# Standalone_Control_Board.net
KiCad netlist of a schematic drawn in EAGLE
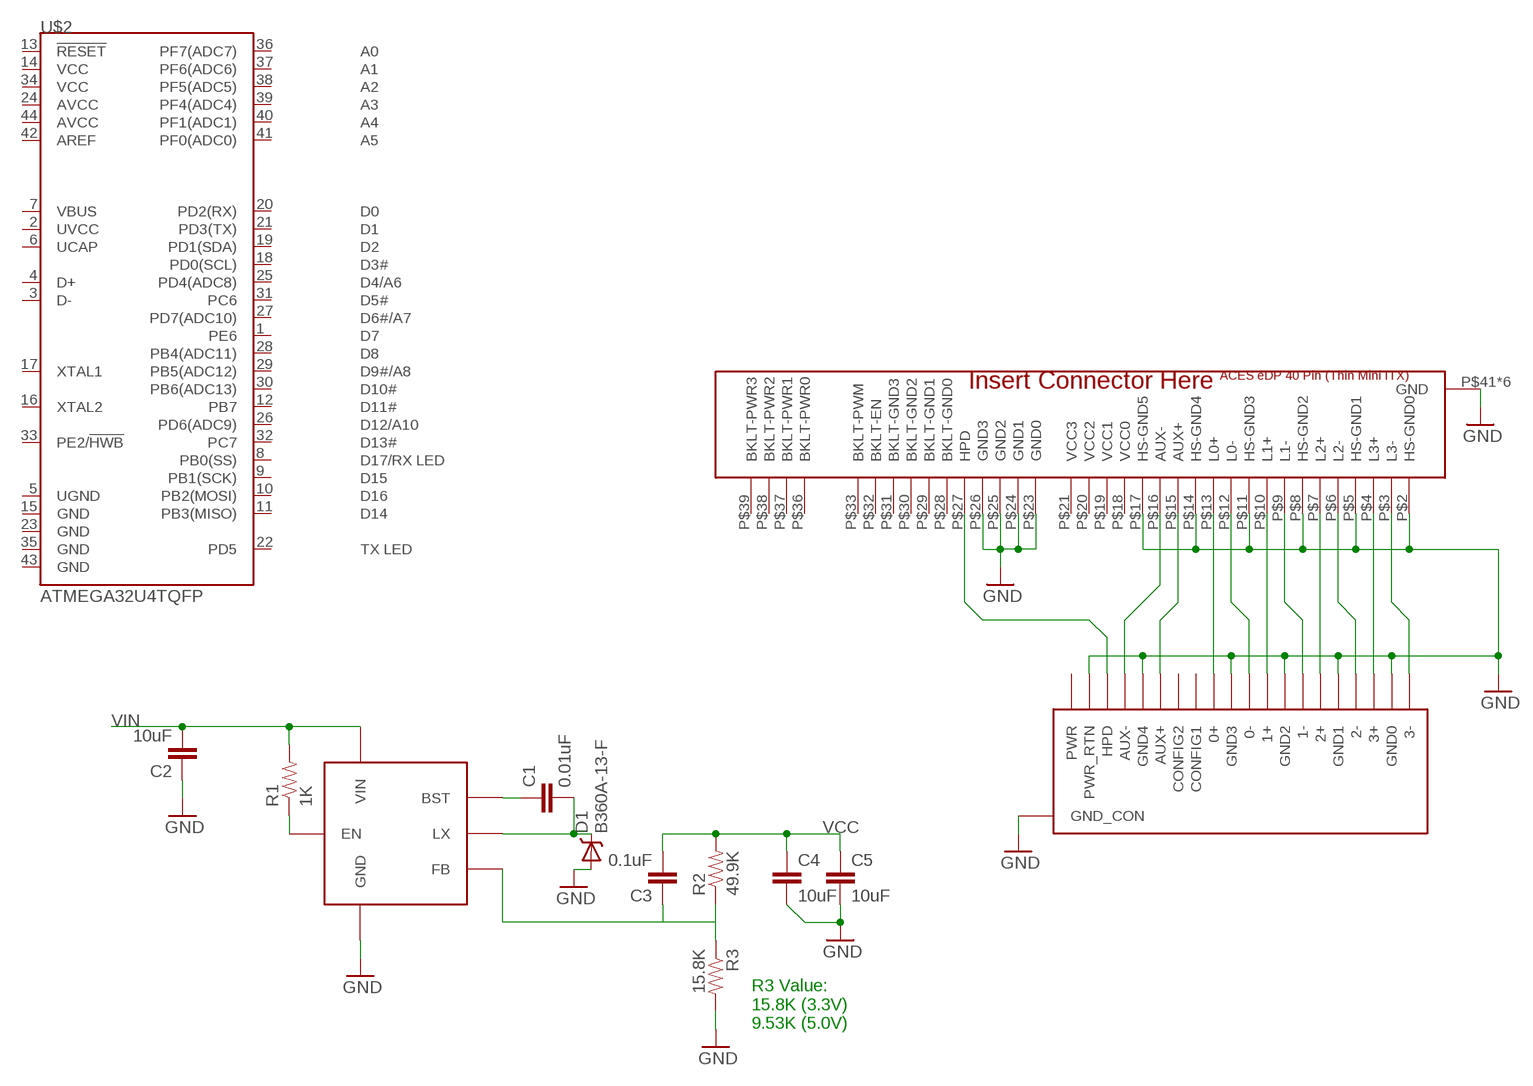
[diagram p0: schematic, sheet 1]

(export (version "E")
  (design (tool "Eeschema 10.0.6"))
  (components
    (comp (ref "C1")
      (value "0.01uF")
      (footprint "eagle-import:0805")
      (libsource (lib "eagle-import") (part "CAP0805"))
    )
    (comp (ref "C2")
      (value "10uF")
      (footprint "eagle-import:0805")
      (libsource (lib "eagle-import") (part "CAP0805"))
    )
    (comp (ref "C3")
      (value "0.1uF")
      (footprint "eagle-import:0805")
      (libsource (lib "eagle-import") (part "CAP0805"))
    )
    (comp (ref "C4")
      (value "10uF")
      (footprint "eagle-import:0805")
      (libsource (lib "eagle-import") (part "CAP0805"))
    )
    (comp (ref "C5")
      (value "10uF")
      (footprint "eagle-import:0805")
      (libsource (lib "eagle-import") (part "CAP0805"))
    )
    (comp (ref "D1")
      (value "B360A-13-F")
      (footprint "eagle-import:SMA-DIODE")
      (libsource (lib "eagle-import") (part "DIODE-SCHOTTKY_"))
    )
    (comp (ref "F1")
      (value "EDP-40PIN-ACES")
      (footprint "eagle-import:ACES-50203-040")
      (libsource (lib "eagle-import") (part "EDP-40PIN-ACES"))
    )
    (comp (ref "R1")
      (value "1K")
      (footprint "eagle-import:0805")
      (libsource (lib "eagle-import") (part "RESISTOR0805-RES"))
    )
    (comp (ref "R2")
      (value "49.9K")
      (footprint "eagle-import:0805")
      (libsource (lib "eagle-import") (part "RESISTOR0805-RES"))
    )
    (comp (ref "R3")
      (value "15.8K")
      (footprint "eagle-import:0805")
      (libsource (lib "eagle-import") (part "RESISTOR0805-RES"))
    )
    (comp (ref "U$1")
      (value "DP-SINK")
      (footprint "eagle-import:MOLEX-47272-0001")
      (libsource (lib "eagle-import") (part "DP-SINK"))
    )
    (comp (ref "U$2")
      (value "ATMEGA32U4TQFP")
      (footprint "eagle-import:SPARKFUN-DIGITALIC_TQFP44")
      (libsource (lib "eagle-import") (part "ATMEGA32U4TQFP"))
    )
    (comp (ref "U$3")
      (value "AOZ1281-BUCK")
      (footprint "eagle-import:2X2-DFN")
      (libsource (lib "eagle-import") (part "AOZ1281-BUCK"))
    )
  )
  (nets
    (net (code "1") (name "/BKLT-GND0") (class "Default")
      (node (ref "F1") (pin "P$28") (pinfunction "BKLT-GND0_P$28") (pintype "power_in"))
    )
    (net (code "2") (name "/BKLT-GND1") (class "Default")
      (node (ref "F1") (pin "P$29") (pinfunction "BKLT-GND1_P$29") (pintype "power_in"))
    )
    (net (code "3") (name "/BKLT-GND2") (class "Default")
      (node (ref "F1") (pin "P$30") (pinfunction "BKLT-GND2_P$30") (pintype "power_in"))
    )
    (net (code "4") (name "/BKLT-GND3") (class "Default")
      (node (ref "F1") (pin "P$31") (pinfunction "BKLT-GND3_P$31") (pintype "power_in"))
    )
    (net (code "5") (name "/BKLT-PWR0") (class "Default")
      (node (ref "F1") (pin "P$36") (pinfunction "BKLT-PWR0_P$36") (pintype "power_in"))
    )
    (net (code "6") (name "/BKLT-PWR1") (class "Default")
      (node (ref "F1") (pin "P$37") (pinfunction "BKLT-PWR1_P$37") (pintype "power_in"))
    )
    (net (code "7") (name "/BKLT-PWR2") (class "Default")
      (node (ref "F1") (pin "P$38") (pinfunction "BKLT-PWR2_P$38") (pintype "power_in"))
    )
    (net (code "8") (name "/BKLT-PWR3") (class "Default")
      (node (ref "F1") (pin "P$39") (pinfunction "BKLT-PWR3_P$39") (pintype "power_in"))
    )
    (net (code "9") (name "/PWR") (class "Default")
      (node (ref "U$1") (pin "P$24") (pinfunction "PWR_P$24") (pintype "power_in"))
    )
    (net (code "10") (name "/VCC") (class "Default")
      (node (ref "C3") (pin "2") (pinfunction "2_2") (pintype "passive"))
      (node (ref "C4") (pin "1") (pinfunction "1_1") (pintype "passive"))
      (node (ref "C5") (pin "1") (pinfunction "1_1") (pintype "passive"))
      (node (ref "R2") (pin "2") (pinfunction "2_2") (pintype "passive"))
    )
    (net (code "11") (name "/VCC0") (class "Default")
      (node (ref "F1") (pin "P$18") (pinfunction "VCC0_P$18") (pintype "power_in"))
    )
    (net (code "12") (name "/VCC1") (class "Default")
      (node (ref "F1") (pin "P$19") (pinfunction "VCC1_P$19") (pintype "power_in"))
    )
    (net (code "13") (name "/VCC2") (class "Default")
      (node (ref "F1") (pin "P$20") (pinfunction "VCC2_P$20") (pintype "power_in"))
    )
    (net (code "14") (name "/VCC3") (class "Default")
      (node (ref "F1") (pin "P$21") (pinfunction "VCC3_P$21") (pintype "power_in"))
    )
    (net (code "15") (name "/VIN") (class "Default")
      (node (ref "C2") (pin "2") (pinfunction "2_2") (pintype "passive"))
      (node (ref "R1") (pin "2") (pinfunction "2_2") (pintype "passive"))
      (node (ref "U$3") (pin "2") (pinfunction "VIN_2") (pintype "bidirectional"))
      (node (ref "U$3") (pin "3") (pinfunction "VIN_3") (pintype "bidirectional"))
    )
    (net (code "16") (name "GND") (class "Default")
      (node (ref "C2") (pin "1") (pinfunction "1_1") (pintype "passive"))
      (node (ref "C4") (pin "2") (pinfunction "2_2") (pintype "passive"))
      (node (ref "C5") (pin "2") (pinfunction "2_2") (pintype "passive"))
      (node (ref "D1") (pin "A") (pinfunction "A_A") (pintype "passive"))
      (node (ref "F1") (pin "P$11") (pinfunction "HS-GND3_P$11") (pintype "tri_state"))
      (node (ref "F1") (pin "P$14") (pinfunction "HS-GND4_P$14") (pintype "tri_state"))
      (node (ref "F1") (pin "P$17") (pinfunction "HS-GND5_P$17") (pintype "tri_state"))
      (node (ref "F1") (pin "P$2") (pinfunction "HS-GND0_P$2") (pintype "tri_state"))
      (node (ref "F1") (pin "P$23") (pinfunction "GND0_P$23") (pintype "power_in"))
      (node (ref "F1") (pin "P$24") (pinfunction "GND1_P$24") (pintype "power_in"))
      (node (ref "F1") (pin "P$25") (pinfunction "GND2_P$25") (pintype "power_in"))
      (node (ref "F1") (pin "P$26") (pinfunction "GND3_P$26") (pintype "power_in"))
      (node (ref "F1") (pin "P$41") (pinfunction "GND_P$41") (pintype "power_in"))
      (node (ref "F1") (pin "P$42") (pinfunction "GND_P$42") (pintype "power_in"))
      (node (ref "F1") (pin "P$43") (pinfunction "GND_P$43") (pintype "power_in"))
      (node (ref "F1") (pin "P$44") (pinfunction "GND_P$44") (pintype "power_in"))
      (node (ref "F1") (pin "P$45") (pinfunction "GND_P$45") (pintype "power_in"))
      (node (ref "F1") (pin "P$46") (pinfunction "GND_P$46") (pintype "power_in"))
      (node (ref "F1") (pin "P$5") (pinfunction "HS-GND1_P$5") (pintype "tri_state"))
      (node (ref "F1") (pin "P$8") (pinfunction "HS-GND2_P$8") (pintype "tri_state"))
      (node (ref "R3") (pin "2") (pinfunction "2_2") (pintype "passive"))
      (node (ref "U$1") (pin "GND1") (pinfunction "GND_CON_GND1") (pintype "power_in"))
      (node (ref "U$1") (pin "GND2") (pinfunction "GND_CON_GND2") (pintype "power_in"))
      (node (ref "U$1") (pin "GND3") (pinfunction "GND_CON_GND3") (pintype "power_in"))
      (node (ref "U$1") (pin "GND4") (pinfunction "GND_CON_GND4") (pintype "power_in"))
      (node (ref "U$1") (pin "P$12") (pinfunction "GND2_P$12") (pintype "power_in"))
      (node (ref "U$1") (pin "P$15") (pinfunction "GND3_P$15") (pintype "power_in"))
      (node (ref "U$1") (pin "P$20") (pinfunction "GND4_P$20") (pintype "power_in"))
      (node (ref "U$1") (pin "P$23") (pinfunction "PWR_RTN_P$23") (pintype "power_in"))
      (node (ref "U$1") (pin "P$6") (pinfunction "GND0_P$6") (pintype "power_in"))
      (node (ref "U$1") (pin "P$9") (pinfunction "GND1_P$9") (pintype "power_in"))
      (node (ref "U$3") (pin "6") (pinfunction "GND_6") (pintype "bidirectional"))
      (node (ref "U$3") (pin "7") (pinfunction "GND_7") (pintype "bidirectional"))
      (node (ref "U$3") (pin "CENTER") (pinfunction "GND_CENTER") (pintype "bidirectional"))
    )
    (net (code "17") (name "Net-(F1-AUX+)") (class "Default")
      (node (ref "F1") (pin "P$15") (pinfunction "AUX+_P$15") (pintype "tri_state"))
      (node (ref "U$1") (pin "P$19") (pinfunction "AUX+_P$19") (pintype "bidirectional"))
    )
    (net (code "18") (name "Net-(F1-AUX-)") (class "Default")
      (node (ref "F1") (pin "P$16") (pinfunction "AUX-_P$16") (pintype "tri_state"))
      (node (ref "U$1") (pin "P$21") (pinfunction "AUX-_P$21") (pintype "bidirectional"))
    )
    (net (code "19") (name "Net-(F1-HPD)") (class "Default")
      (node (ref "F1") (pin "P$27") (pinfunction "HPD_P$27") (pintype "bidirectional"))
      (node (ref "U$1") (pin "P$22") (pinfunction "HPD_P$22") (pintype "output"))
    )
    (net (code "20") (name "Net-(F1-L0+)") (class "Default")
      (node (ref "F1") (pin "P$13") (pinfunction "L0+_P$13") (pintype "tri_state"))
      (node (ref "U$1") (pin "P$16") (pinfunction "0+_P$16") (pintype "input"))
    )
    (net (code "21") (name "Net-(F1-L0-)") (class "Default")
      (node (ref "F1") (pin "P$12") (pinfunction "L0-_P$12") (pintype "tri_state"))
      (node (ref "U$1") (pin "P$14") (pinfunction "0-_P$14") (pintype "input"))
    )
    (net (code "22") (name "Net-(F1-L1+)") (class "Default")
      (node (ref "F1") (pin "P$10") (pinfunction "L1+_P$10") (pintype "tri_state"))
      (node (ref "U$1") (pin "P$13") (pinfunction "1+_P$13") (pintype "input"))
    )
    (net (code "23") (name "Net-(F1-L1-)") (class "Default")
      (node (ref "F1") (pin "P$9") (pinfunction "L1-_P$9") (pintype "tri_state"))
      (node (ref "U$1") (pin "P$11") (pinfunction "1-_P$11") (pintype "input"))
    )
    (net (code "24") (name "Net-(F1-L2+)") (class "Default")
      (node (ref "F1") (pin "P$7") (pinfunction "L2+_P$7") (pintype "tri_state"))
      (node (ref "U$1") (pin "P$10") (pinfunction "2+_P$10") (pintype "input"))
    )
    (net (code "25") (name "Net-(F1-L2-)") (class "Default")
      (node (ref "F1") (pin "P$6") (pinfunction "L2-_P$6") (pintype "tri_state"))
      (node (ref "U$1") (pin "P$8") (pinfunction "2-_P$8") (pintype "input"))
    )
    (net (code "26") (name "Net-(F1-L3+)") (class "Default")
      (node (ref "F1") (pin "P$4") (pinfunction "L3+_P$4") (pintype "tri_state"))
      (node (ref "U$1") (pin "P$7") (pinfunction "3+_P$7") (pintype "input"))
    )
    (net (code "27") (name "Net-(F1-L3-)") (class "Default")
      (node (ref "F1") (pin "P$3") (pinfunction "L3-_P$3") (pintype "tri_state"))
      (node (ref "U$1") (pin "P$5") (pinfunction "3-_P$5") (pintype "input"))
    )
    (net (code "28") (name "Net-(R2-Pad1)") (class "Default")
      (node (ref "R2") (pin "1") (pinfunction "1_1") (pintype "passive"))
      (node (ref "R3") (pin "1") (pinfunction "1_1") (pintype "passive"))
    )
    (net (code "29") (name "Net-(U$3-BST)") (class "Default")
      (node (ref "C1") (pin "1") (pinfunction "1_1") (pintype "passive"))
      (node (ref "U$3") (pin "8") (pinfunction "BST_8") (pintype "bidirectional"))
    )
    (net (code "30") (name "Net-(U$3-EN)") (class "Default")
      (node (ref "R1") (pin "1") (pinfunction "1_1") (pintype "passive"))
      (node (ref "U$3") (pin "4") (pinfunction "EN_4") (pintype "bidirectional"))
    )
    (net (code "31") (name "Net-(U$3-FB)") (class "Default")
      (node (ref "C3") (pin "1") (pinfunction "1_1") (pintype "passive"))
      (node (ref "U$3") (pin "5") (pinfunction "FB_5") (pintype "bidirectional"))
    )
    (net (code "32") (name "Net-(U$3-LX)") (class "Default")
      (node (ref "C1") (pin "2") (pinfunction "2_2") (pintype "passive"))
      (node (ref "D1") (pin "C") (pinfunction "C_C") (pintype "passive"))
      (node (ref "U$3") (pin "1") (pinfunction "LX_1") (pintype "bidirectional"))
    )
    (net (code "33") (name "unconnected-(F1-BKLT-EN-PadP$32)") (class "Default")
      (node (ref "F1") (pin "P$32") (pinfunction "BKLT-EN_P$32") (pintype "bidirectional"))
    )
    (net (code "34") (name "unconnected-(F1-BKLT-PWM-PadP$33)") (class "Default")
      (node (ref "F1") (pin "P$33") (pinfunction "BKLT-PWM_P$33") (pintype "bidirectional"))
    )
    (net (code "35") (name "unconnected-(U$1-CONFIG1-PadP$17)") (class "Default")
      (node (ref "U$1") (pin "P$17") (pinfunction "CONFIG1_P$17") (pintype "bidirectional"))
    )
    (net (code "36") (name "unconnected-(U$1-CONFIG2-PadP$18)") (class "Default")
      (node (ref "U$1") (pin "P$18") (pinfunction "CONFIG2_P$18") (pintype "bidirectional"))
    )
    (net (code "37") (name "unconnected-(U$2-AREF-Pad42)") (class "Default")
      (node (ref "U$2") (pin "42") (pinfunction "AREF_42") (pintype "bidirectional"))
    )
    (net (code "38") (name "unconnected-(U$2-AVCC-Pad24)") (class "Default")
      (node (ref "U$2") (pin "24") (pinfunction "AVCC_24") (pintype "bidirectional"))
    )
    (net (code "39") (name "unconnected-(U$2-AVCC-Pad44)") (class "Default")
      (node (ref "U$2") (pin "44") (pinfunction "AVCC_44") (pintype "bidirectional"))
    )
    (net (code "40") (name "unconnected-(U$2-D+-Pad4)") (class "Default")
      (node (ref "U$2") (pin "4") (pinfunction "D+_4") (pintype "bidirectional"))
    )
    (net (code "41") (name "unconnected-(U$2-D--Pad3)") (class "Default")
      (node (ref "U$2") (pin "3") (pinfunction "D-_3") (pintype "bidirectional"))
    )
    (net (code "42") (name "unconnected-(U$2-GND-Pad15)") (class "Default")
      (node (ref "U$2") (pin "15") (pinfunction "GND_15") (pintype "bidirectional"))
    )
    (net (code "43") (name "unconnected-(U$2-GND-Pad23)") (class "Default")
      (node (ref "U$2") (pin "23") (pinfunction "GND_23") (pintype "bidirectional"))
    )
    (net (code "44") (name "unconnected-(U$2-GND-Pad35)") (class "Default")
      (node (ref "U$2") (pin "35") (pinfunction "GND_35") (pintype "bidirectional"))
    )
    (net (code "45") (name "unconnected-(U$2-GND-Pad43)") (class "Default")
      (node (ref "U$2") (pin "43") (pinfunction "GND_43") (pintype "bidirectional"))
    )
    (net (code "46") (name "unconnected-(U$2-PB0(SS)-Pad8)") (class "Default")
      (node (ref "U$2") (pin "8") (pinfunction "PB0(SS)_8") (pintype "bidirectional"))
    )
    (net (code "47") (name "unconnected-(U$2-PB1(SCK)-Pad9)") (class "Default")
      (node (ref "U$2") (pin "9") (pinfunction "PB1(SCK)_9") (pintype "bidirectional"))
    )
    (net (code "48") (name "unconnected-(U$2-PB2(MOSI)-Pad10)") (class "Default")
      (node (ref "U$2") (pin "10") (pinfunction "PB2(MOSI)_10") (pintype "bidirectional"))
    )
    (net (code "49") (name "unconnected-(U$2-PB3(MISO)-Pad11)") (class "Default")
      (node (ref "U$2") (pin "11") (pinfunction "PB3(MISO)_11") (pintype "bidirectional"))
    )
    (net (code "50") (name "unconnected-(U$2-PB4(ADC11)-Pad28)") (class "Default")
      (node (ref "U$2") (pin "28") (pinfunction "PB4(ADC11)_28") (pintype "bidirectional"))
    )
    (net (code "51") (name "unconnected-(U$2-PB5(ADC12)-Pad29)") (class "Default")
      (node (ref "U$2") (pin "29") (pinfunction "PB5(ADC12)_29") (pintype "bidirectional"))
    )
    (net (code "52") (name "unconnected-(U$2-PB6(ADC13)-Pad30)") (class "Default")
      (node (ref "U$2") (pin "30") (pinfunction "PB6(ADC13)_30") (pintype "bidirectional"))
    )
    (net (code "53") (name "unconnected-(U$2-PB7-Pad12)") (class "Default")
      (node (ref "U$2") (pin "12") (pinfunction "PB7_12") (pintype "bidirectional"))
    )
    (net (code "54") (name "unconnected-(U$2-PC6-Pad31)") (class "Default")
      (node (ref "U$2") (pin "31") (pinfunction "PC6_31") (pintype "bidirectional"))
    )
    (net (code "55") (name "unconnected-(U$2-PC7-Pad32)") (class "Default")
      (node (ref "U$2") (pin "32") (pinfunction "PC7_32") (pintype "bidirectional"))
    )
    (net (code "56") (name "unconnected-(U$2-PD0(SCL)-Pad18)") (class "Default")
      (node (ref "U$2") (pin "18") (pinfunction "PD0(SCL)_18") (pintype "bidirectional"))
    )
    (net (code "57") (name "unconnected-(U$2-PD1(SDA)-Pad19)") (class "Default")
      (node (ref "U$2") (pin "19") (pinfunction "PD1(SDA)_19") (pintype "bidirectional"))
    )
    (net (code "58") (name "unconnected-(U$2-PD2(RX)-Pad20)") (class "Default")
      (node (ref "U$2") (pin "20") (pinfunction "PD2(RX)_20") (pintype "bidirectional"))
    )
    (net (code "59") (name "unconnected-(U$2-PD3(TX)-Pad21)") (class "Default")
      (node (ref "U$2") (pin "21") (pinfunction "PD3(TX)_21") (pintype "bidirectional"))
    )
    (net (code "60") (name "unconnected-(U$2-PD4(ADC8)-Pad25)") (class "Default")
      (node (ref "U$2") (pin "25") (pinfunction "PD4(ADC8)_25") (pintype "bidirectional"))
    )
    (net (code "61") (name "unconnected-(U$2-PD5-Pad22)") (class "Default")
      (node (ref "U$2") (pin "22") (pinfunction "PD5_22") (pintype "bidirectional"))
    )
    (net (code "62") (name "unconnected-(U$2-PD6(ADC9)-Pad26)") (class "Default")
      (node (ref "U$2") (pin "26") (pinfunction "PD6(ADC9)_26") (pintype "bidirectional"))
    )
    (net (code "63") (name "unconnected-(U$2-PD7(ADC10)-Pad27)") (class "Default")
      (node (ref "U$2") (pin "27") (pinfunction "PD7(ADC10)_27") (pintype "bidirectional"))
    )
    (net (code "64") (name "unconnected-(U$2-PE2{slash}~{HWB}-Pad33)") (class "Default")
      (node (ref "U$2") (pin "33") (pinfunction "PE2/~{HWB}_33") (pintype "bidirectional"))
    )
    (net (code "65") (name "unconnected-(U$2-PE6-Pad1)") (class "Default")
      (node (ref "U$2") (pin "1") (pinfunction "PE6_1") (pintype "bidirectional"))
    )
    (net (code "66") (name "unconnected-(U$2-PF0(ADC0)-Pad41)") (class "Default")
      (node (ref "U$2") (pin "41") (pinfunction "PF0(ADC0)_41") (pintype "bidirectional"))
    )
    (net (code "67") (name "unconnected-(U$2-PF1(ADC1)-Pad40)") (class "Default")
      (node (ref "U$2") (pin "40") (pinfunction "PF1(ADC1)_40") (pintype "bidirectional"))
    )
    (net (code "68") (name "unconnected-(U$2-PF4(ADC4)-Pad39)") (class "Default")
      (node (ref "U$2") (pin "39") (pinfunction "PF4(ADC4)_39") (pintype "bidirectional"))
    )
    (net (code "69") (name "unconnected-(U$2-PF5(ADC5)-Pad38)") (class "Default")
      (node (ref "U$2") (pin "38") (pinfunction "PF5(ADC5)_38") (pintype "bidirectional"))
    )
    (net (code "70") (name "unconnected-(U$2-PF6(ADC6)-Pad37)") (class "Default")
      (node (ref "U$2") (pin "37") (pinfunction "PF6(ADC6)_37") (pintype "bidirectional"))
    )
    (net (code "71") (name "unconnected-(U$2-PF7(ADC7)-Pad36)") (class "Default")
      (node (ref "U$2") (pin "36") (pinfunction "PF7(ADC7)_36") (pintype "bidirectional"))
    )
    (net (code "72") (name "unconnected-(U$2-UCAP-Pad6)") (class "Default")
      (node (ref "U$2") (pin "6") (pinfunction "UCAP_6") (pintype "bidirectional"))
    )
    (net (code "73") (name "unconnected-(U$2-UGND-Pad5)") (class "Default")
      (node (ref "U$2") (pin "5") (pinfunction "UGND_5") (pintype "bidirectional"))
    )
    (net (code "74") (name "unconnected-(U$2-UVCC-Pad2)") (class "Default")
      (node (ref "U$2") (pin "2") (pinfunction "UVCC_2") (pintype "bidirectional"))
    )
    (net (code "75") (name "unconnected-(U$2-VBUS-Pad7)") (class "Default")
      (node (ref "U$2") (pin "7") (pinfunction "VBUS_7") (pintype "bidirectional"))
    )
    (net (code "76") (name "unconnected-(U$2-VCC-Pad14)") (class "Default")
      (node (ref "U$2") (pin "14") (pinfunction "VCC_14") (pintype "bidirectional"))
    )
    (net (code "77") (name "unconnected-(U$2-VCC-Pad34)") (class "Default")
      (node (ref "U$2") (pin "34") (pinfunction "VCC_34") (pintype "bidirectional"))
    )
    (net (code "78") (name "unconnected-(U$2-XTAL1-Pad17)") (class "Default")
      (node (ref "U$2") (pin "17") (pinfunction "XTAL1_17") (pintype "bidirectional"))
    )
    (net (code "79") (name "unconnected-(U$2-XTAL2-Pad16)") (class "Default")
      (node (ref "U$2") (pin "16") (pinfunction "XTAL2_16") (pintype "bidirectional"))
    )
    (net (code "80") (name "unconnected-(U$2-~{RESET}-Pad13)") (class "Default")
      (node (ref "U$2") (pin "13") (pinfunction "~{RESET}_13") (pintype "bidirectional"))
    )
  )
)
